# Nakuja_Remix_2.net
KiCad netlist of a schematic drawn in EasyEDA
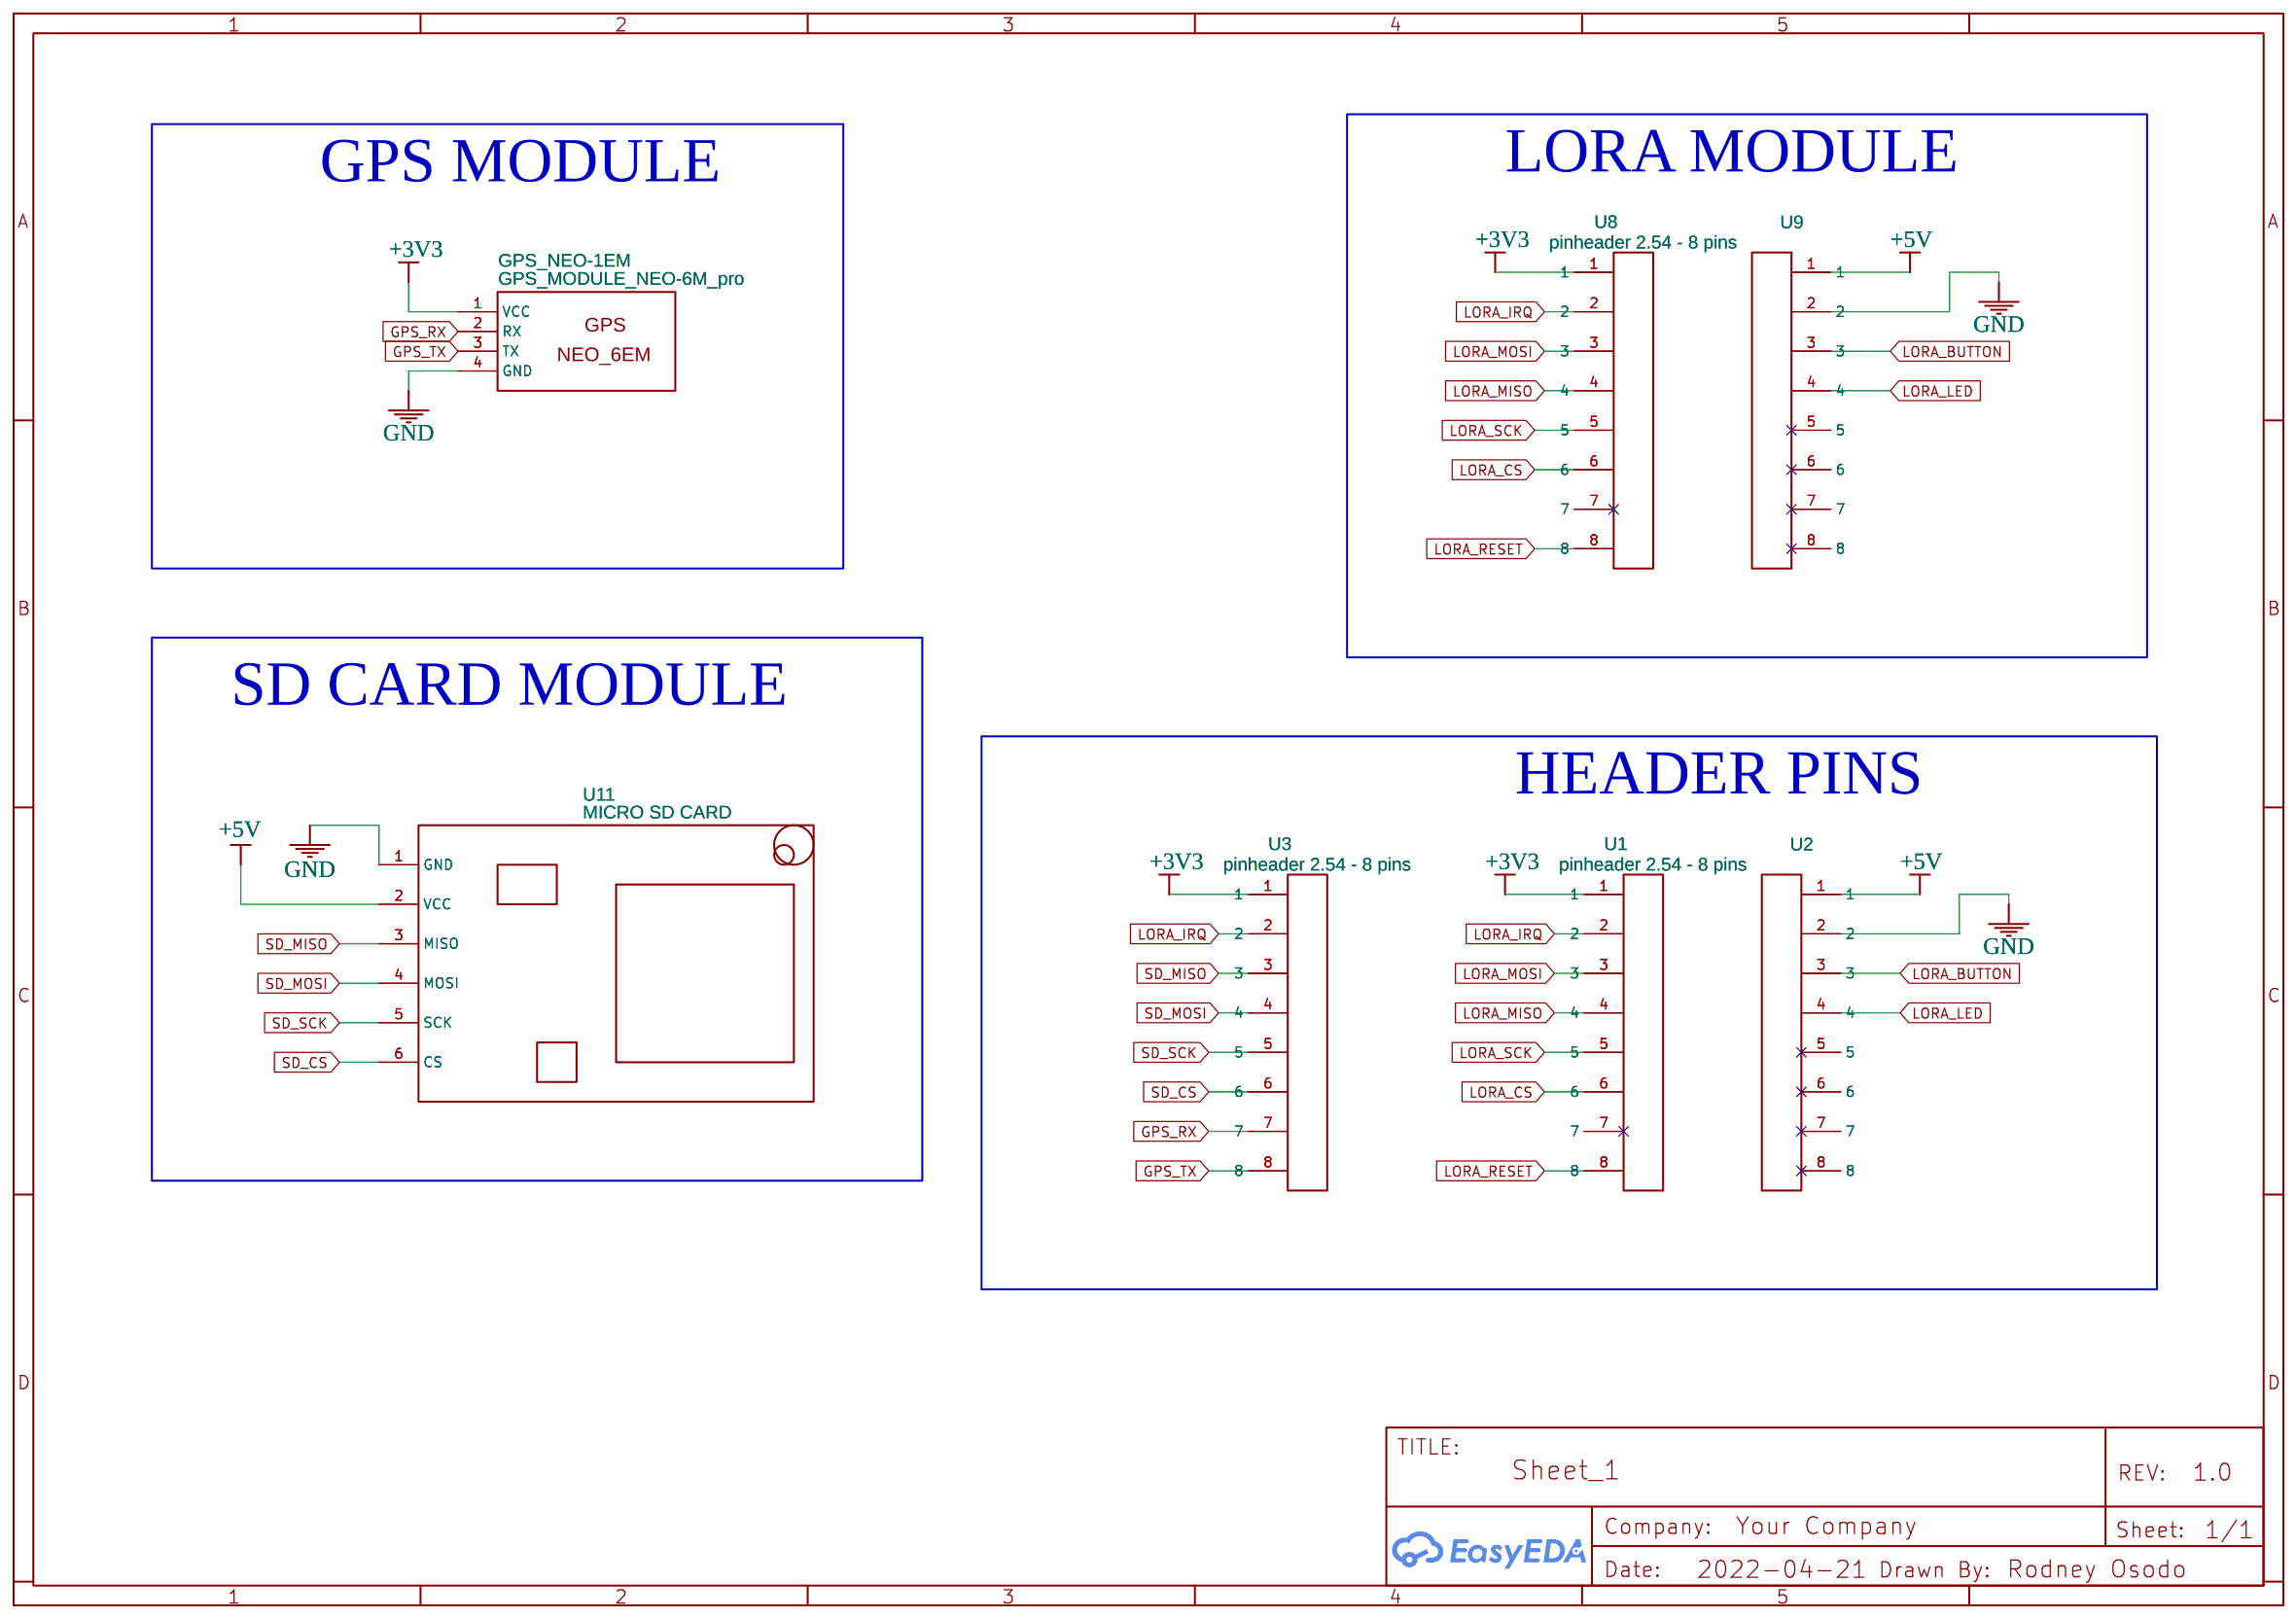
[diagram p0: schematic sheet]

(export (version "E")
  (design (tool "Eeschema 10.0.6"))
  (components
    (comp (ref "GPS_NEO-1EM")
      (value "GPS_MODULE_NEO-6M_pro")
      (libsource (lib "") (part "GPS_MODULE_NEO-6M_pro"))
    )
    (comp (ref "U1") (value "pinheader 2.54 - 8 pins") (libsource (lib "") (part "pinheader 2.54 - 8 pins")))
    (comp (ref "U2")
      (value "pinheader 2.54 - 8 pins")
      (libsource (lib "") (part "pinheader 2.54 - 8 pins_1"))
    )
    (comp (ref "U3") (value "pinheader 2.54 - 8 pins") (libsource (lib "") (part "pinheader 2.54 - 8 pins")))
    (comp (ref "U8") (value "pinheader 2.54 - 8 pins") (libsource (lib "") (part "pinheader 2.54 - 8 pins")))
    (comp (ref "U9")
      (value "pinheader 2.54 - 8 pins")
      (libsource (lib "") (part "pinheader 2.54 - 8 pins_1"))
    )
    (comp (ref "U11") (value "MICRO SD CARD") (libsource (lib "") (part "MICRO SD CARD")))
  )
  (nets
    (net (code "1") (name "+3V3") (class "Default")
      (node (ref "GPS_NEO-1EM") (pin "1") (pinfunction "VCC_1") (pintype "passive"))
      (node (ref "U1") (pin "1") (pinfunction "1_1") (pintype "unspecified"))
      (node (ref "U3") (pin "1") (pinfunction "1_1") (pintype "unspecified"))
      (node (ref "U8") (pin "1") (pinfunction "1_1") (pintype "unspecified"))
    )
    (net (code "2") (name "+5V") (class "Default")
      (node (ref "U11") (pin "2") (pinfunction "VCC_2") (pintype "unspecified"))
      (node (ref "U2") (pin "1") (pinfunction "1_1") (pintype "unspecified"))
      (node (ref "U9") (pin "1") (pinfunction "1_1") (pintype "unspecified"))
    )
    (net (code "3") (name "GND") (class "Default")
      (node (ref "GPS_NEO-1EM") (pin "4") (pinfunction "GND_4") (pintype "passive"))
      (node (ref "U11") (pin "1") (pinfunction "GND_1") (pintype "unspecified"))
      (node (ref "U2") (pin "2") (pinfunction "2_2") (pintype "unspecified"))
      (node (ref "U9") (pin "2") (pinfunction "2_2") (pintype "unspecified"))
    )
    (net (code "4") (name "GPS_RX") (class "Default")
      (node (ref "GPS_NEO-1EM") (pin "2") (pinfunction "RX_2") (pintype "input"))
      (node (ref "U3") (pin "7") (pinfunction "7_7") (pintype "unspecified"))
    )
    (net (code "5") (name "GPS_TX") (class "Default")
      (node (ref "GPS_NEO-1EM") (pin "3") (pinfunction "TX_3") (pintype "output"))
      (node (ref "U3") (pin "8") (pinfunction "8_8") (pintype "unspecified"))
    )
    (net (code "6") (name "LORA_BUTTON") (class "Default")
      (node (ref "U2") (pin "3") (pinfunction "3_3") (pintype "unspecified"))
      (node (ref "U9") (pin "3") (pinfunction "3_3") (pintype "unspecified"))
    )
    (net (code "7") (name "LORA_CS") (class "Default")
      (node (ref "U1") (pin "6") (pinfunction "6_6") (pintype "unspecified"))
      (node (ref "U8") (pin "6") (pinfunction "6_6") (pintype "unspecified"))
    )
    (net (code "8") (name "LORA_IRQ") (class "Default")
      (node (ref "U1") (pin "2") (pinfunction "2_2") (pintype "unspecified"))
      (node (ref "U3") (pin "2") (pinfunction "2_2") (pintype "unspecified"))
      (node (ref "U8") (pin "2") (pinfunction "2_2") (pintype "unspecified"))
    )
    (net (code "9") (name "LORA_LED") (class "Default")
      (node (ref "U2") (pin "4") (pinfunction "4_4") (pintype "unspecified"))
      (node (ref "U9") (pin "4") (pinfunction "4_4") (pintype "unspecified"))
    )
    (net (code "10") (name "LORA_MISO") (class "Default")
      (node (ref "U1") (pin "4") (pinfunction "4_4") (pintype "unspecified"))
      (node (ref "U8") (pin "4") (pinfunction "4_4") (pintype "unspecified"))
    )
    (net (code "11") (name "LORA_MOSI") (class "Default")
      (node (ref "U1") (pin "3") (pinfunction "3_3") (pintype "unspecified"))
      (node (ref "U8") (pin "3") (pinfunction "3_3") (pintype "unspecified"))
    )
    (net (code "12") (name "LORA_RESET") (class "Default")
      (node (ref "U1") (pin "8") (pinfunction "8_8") (pintype "unspecified"))
      (node (ref "U8") (pin "8") (pinfunction "8_8") (pintype "unspecified"))
    )
    (net (code "13") (name "LORA_SCK") (class "Default")
      (node (ref "U1") (pin "5") (pinfunction "5_5") (pintype "unspecified"))
      (node (ref "U8") (pin "5") (pinfunction "5_5") (pintype "unspecified"))
    )
    (net (code "14") (name "SD_CS") (class "Default")
      (node (ref "U11") (pin "6") (pinfunction "CS_6") (pintype "unspecified"))
      (node (ref "U3") (pin "6") (pinfunction "6_6") (pintype "unspecified"))
    )
    (net (code "15") (name "SD_MISO") (class "Default")
      (node (ref "U11") (pin "3") (pinfunction "MISO_3") (pintype "unspecified"))
      (node (ref "U3") (pin "3") (pinfunction "3_3") (pintype "unspecified"))
    )
    (net (code "16") (name "SD_MOSI") (class "Default")
      (node (ref "U11") (pin "4") (pinfunction "MOSI_4") (pintype "unspecified"))
      (node (ref "U3") (pin "4") (pinfunction "4_4") (pintype "unspecified"))
    )
    (net (code "17") (name "SD_SCK") (class "Default")
      (node (ref "U11") (pin "5") (pinfunction "SCK_5") (pintype "unspecified"))
      (node (ref "U3") (pin "5") (pinfunction "5_5") (pintype "unspecified"))
    )
    (net (code "18") (name "unconnected-(U1-Pad7)") (class "Default")
      (node (ref "U1") (pin "7") (pinfunction "7_7") (pintype "unspecified+no_connect"))
    )
    (net (code "19") (name "unconnected-(U2-Pad5)") (class "Default")
      (node (ref "U2") (pin "5") (pinfunction "5_5") (pintype "unspecified+no_connect"))
    )
    (net (code "20") (name "unconnected-(U2-Pad6)") (class "Default")
      (node (ref "U2") (pin "6") (pinfunction "6_6") (pintype "unspecified+no_connect"))
    )
    (net (code "21") (name "unconnected-(U2-Pad7)") (class "Default")
      (node (ref "U2") (pin "7") (pinfunction "7_7") (pintype "unspecified+no_connect"))
    )
    (net (code "22") (name "unconnected-(U2-Pad8)") (class "Default")
      (node (ref "U2") (pin "8") (pinfunction "8_8") (pintype "unspecified+no_connect"))
    )
    (net (code "23") (name "unconnected-(U8-Pad7)") (class "Default")
      (node (ref "U8") (pin "7") (pinfunction "7_7") (pintype "unspecified+no_connect"))
    )
    (net (code "24") (name "unconnected-(U9-Pad5)") (class "Default")
      (node (ref "U9") (pin "5") (pinfunction "5_5") (pintype "unspecified+no_connect"))
    )
    (net (code "25") (name "unconnected-(U9-Pad6)") (class "Default")
      (node (ref "U9") (pin "6") (pinfunction "6_6") (pintype "unspecified+no_connect"))
    )
    (net (code "26") (name "unconnected-(U9-Pad7)") (class "Default")
      (node (ref "U9") (pin "7") (pinfunction "7_7") (pintype "unspecified+no_connect"))
    )
    (net (code "27") (name "unconnected-(U9-Pad8)") (class "Default")
      (node (ref "U9") (pin "8") (pinfunction "8_8") (pintype "unspecified+no_connect"))
    )
  )
)
